# Grove_-_Sound_Sensor_v1_6.net
KiCad netlist of a schematic drawn in EAGLE
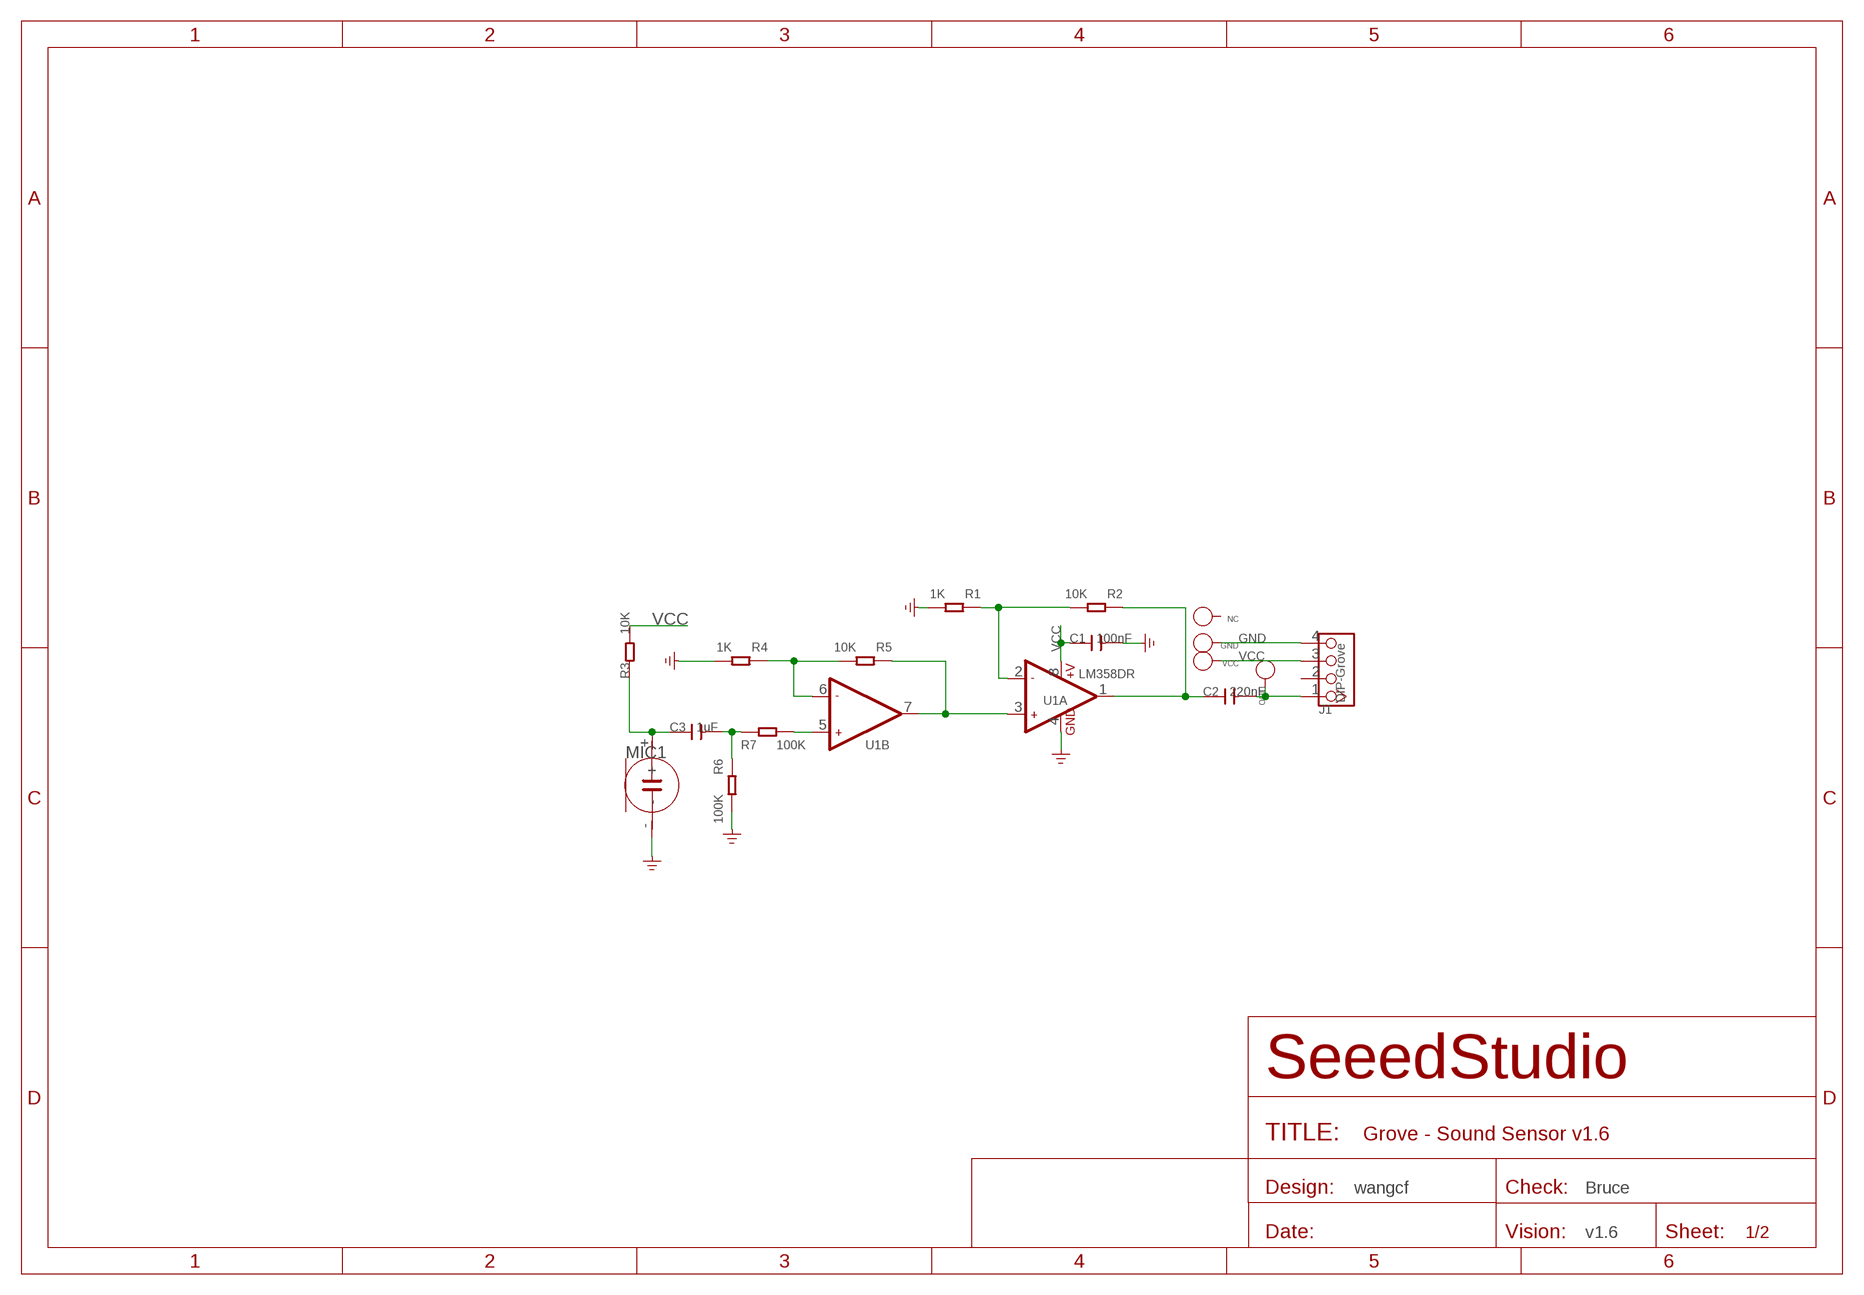
[diagram p0: schematic, sheet 1]
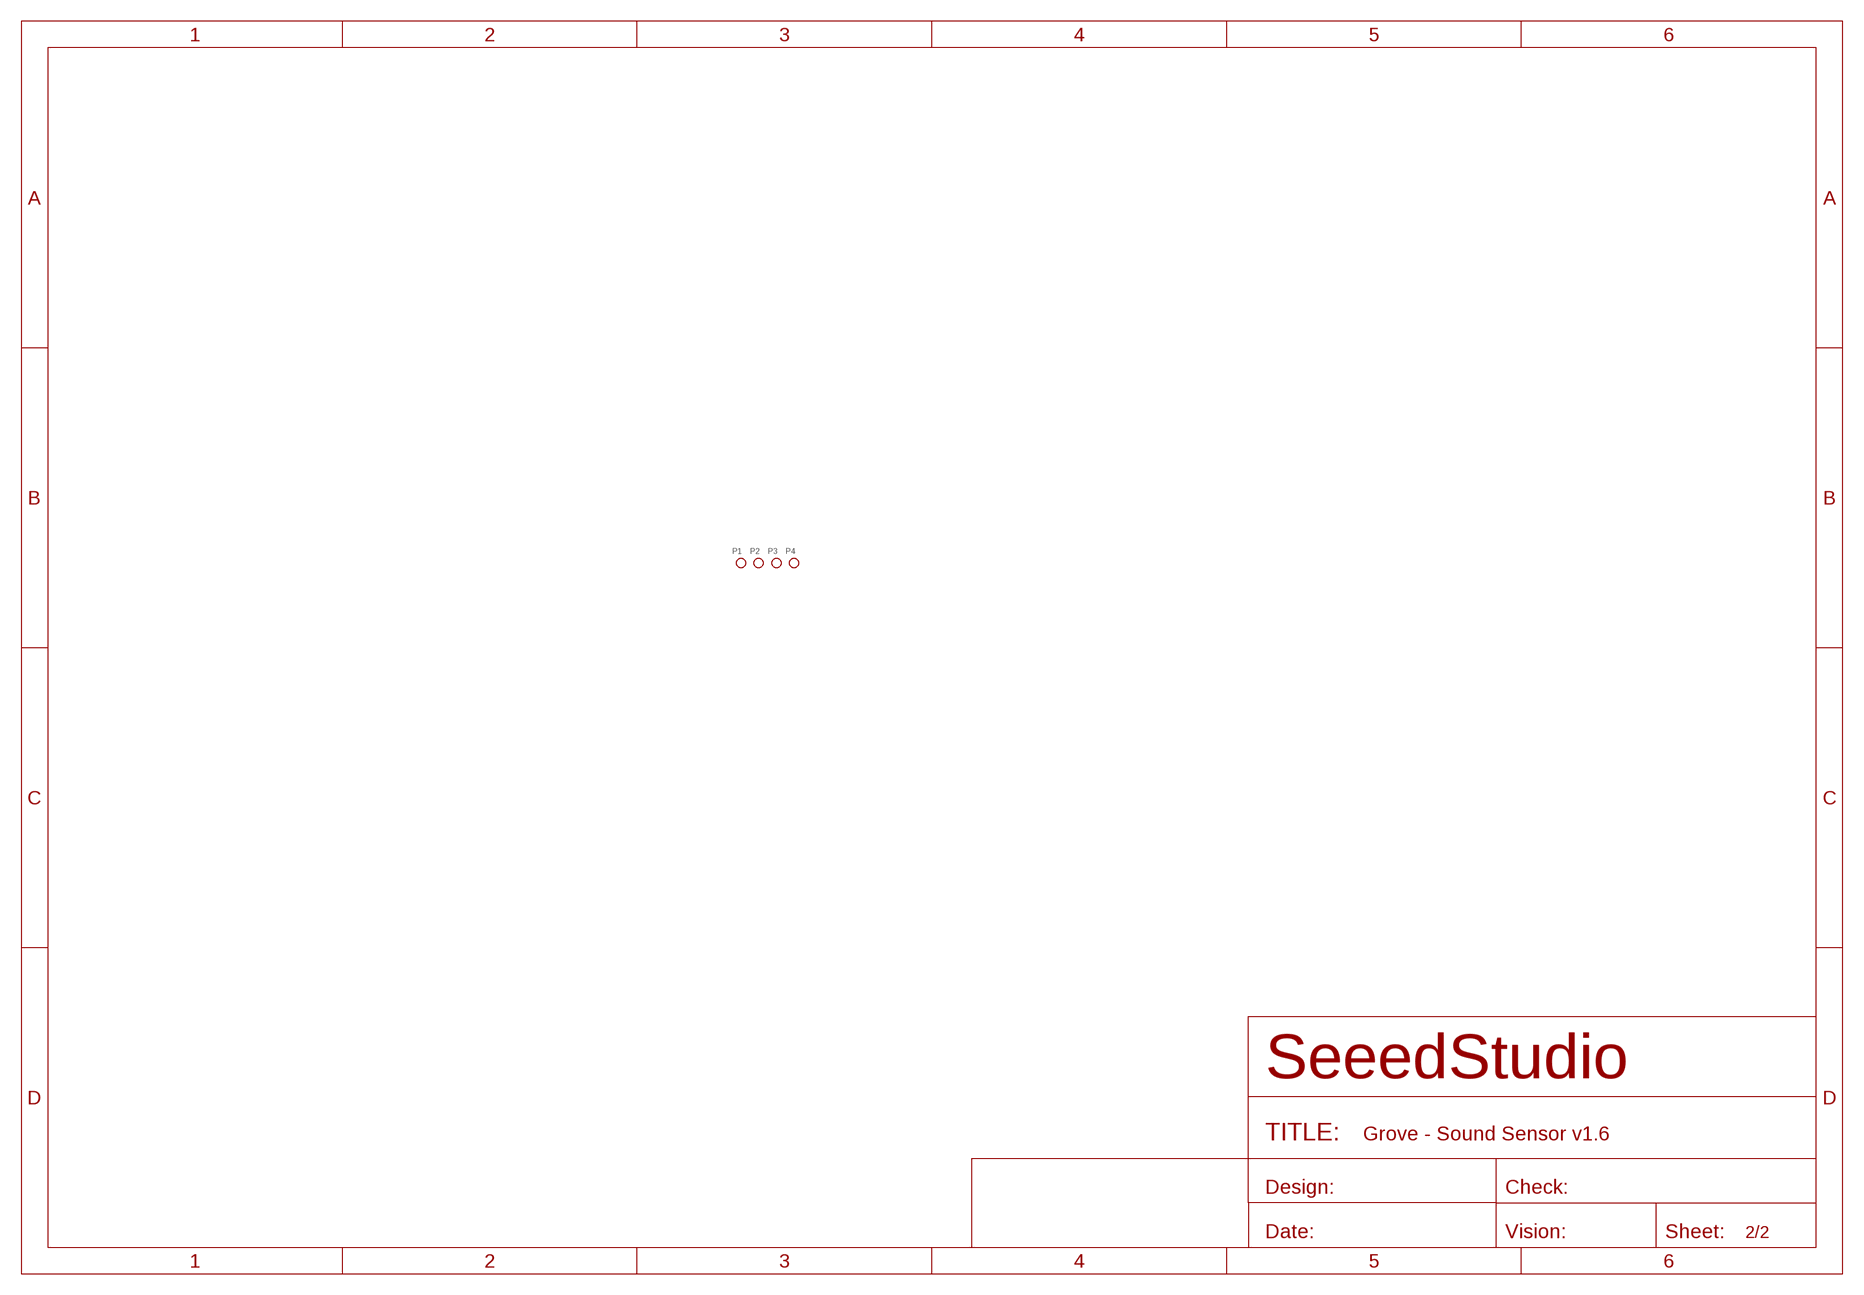
[diagram p1: schematic, sheet 2]

(export (version "E")
  (design (tool "Eeschema 10.0.6"))
  (components
    (comp (ref "P1")
      (value "PAD-MARK")
      (footprint "eagle-import:ROUND-MARK-1.0")
      (fields (field (name "PARTNO") "DNP"))
      (libsource (lib "eagle-import") (part "PAD-MARK"))
    )
    (comp (ref "P2")
      (value "PAD-MARK")
      (footprint "eagle-import:ROUND-MARK-1.0")
      (fields (field (name "PARTNO") "DNP"))
      (libsource (lib "eagle-import") (part "PAD-MARK"))
    )
    (comp (ref "P3")
      (value "PAD-MARK")
      (footprint "eagle-import:ROUND-MARK-1.0")
      (fields (field (name "PARTNO") "DNP"))
      (libsource (lib "eagle-import") (part "PAD-MARK"))
    )
    (comp (ref "P4")
      (value "PAD-MARK")
      (footprint "eagle-import:ROUND-MARK-1.0")
      (fields (field (name "PARTNO") "DNP"))
      (libsource (lib "eagle-import") (part "PAD-MARK"))
    )
    (comp (ref "C1")
      (value "100nF")
      (footprint "eagle-import:C0603")
      (libsource (lib "eagle-import") (part "C-0603"))
    )
    (comp (ref "C2")
      (value "220nF")
      (footprint "eagle-import:C0603")
      (libsource (lib "eagle-import") (part "C-0603"))
    )
    (comp (ref "C3")
      (value "1uF")
      (footprint "eagle-import:C0603")
      (libsource (lib "eagle-import") (part "C-0603"))
    )
    (comp (ref "GND")
      (value "PAD-TEST-POINT'4545'")
      (footprint "eagle-import:TP_4545")
      (fields (field (name "PARTNO") "DNP"))
      (libsource (lib "eagle-import") (part "PAD-TEST-POINT'4545'"))
    )
    (comp (ref "J1")
      (value "DIP-Grove")
      (footprint "eagle-import:4P-2.0")
      (libsource (lib "eagle-import") (part "TWIG-4P-2.0-2.0"))
    )
    (comp (ref "MIC1")
      (value "MICROPHONE'KS-9745P,-56DB'")
      (footprint "eagle-import:2P-D9.7_4.5H")
      (libsource (lib "eagle-import") (part "MICROPHONE'KS-9745P,-56DB'"))
    )
    (comp (ref "NC")
      (value "PAD-TEST-POINT'4545'")
      (footprint "eagle-import:TP_4545")
      (fields (field (name "PARTNO") "DNP"))
      (libsource (lib "eagle-import") (part "PAD-TEST-POINT'4545'"))
    )
    (comp (ref "OUT")
      (value "PAD-TEST-POINT'4545'")
      (footprint "eagle-import:TP_4545")
      (fields (field (name "PARTNO") "DNP"))
      (libsource (lib "eagle-import") (part "PAD-TEST-POINT'4545'"))
    )
    (comp (ref "R1")
      (value "1K")
      (footprint "eagle-import:R0603")
      (libsource (lib "eagle-import") (part "R-0603"))
    )
    (comp (ref "R2")
      (value "10K")
      (footprint "eagle-import:R0603")
      (libsource (lib "eagle-import") (part "R-0603"))
    )
    (comp (ref "R3")
      (value "10K")
      (footprint "eagle-import:R0603")
      (libsource (lib "eagle-import") (part "R-0603"))
    )
    (comp (ref "R4")
      (value "1K")
      (footprint "eagle-import:R0603")
      (libsource (lib "eagle-import") (part "R-0603"))
    )
    (comp (ref "R5")
      (value "10K")
      (footprint "eagle-import:R0603")
      (libsource (lib "eagle-import") (part "R-0603"))
    )
    (comp (ref "R6")
      (value "100K")
      (footprint "eagle-import:R0603")
      (libsource (lib "eagle-import") (part "R-0603"))
    )
    (comp (ref "R7")
      (value "100K")
      (footprint "eagle-import:R0603")
      (libsource (lib "eagle-import") (part "R-0603"))
    )
    (comp (ref "U1")
      (value "LM358DR")
      (footprint "eagle-import:SO08")
      (libsource (lib "eagle-import") (part "LMV358D"))
    )
    (comp (ref "VCC")
      (value "PAD-TEST-POINT'4545'")
      (footprint "eagle-import:TP_4545")
      (fields (field (name "PARTNO") "DNP"))
      (libsource (lib "eagle-import") (part "PAD-TEST-POINT'4545'"))
    )
  )
  (nets
    (net (code "1") (name "GND") (class "Default")
      (node (ref "C1") (pin "2") (pinfunction "2_2") (pintype "passive"))
      (node (ref "GND") (pin "T") (pinfunction "T_T") (pintype "bidirectional"))
      (node (ref "J1") (pin "4") (pinfunction "4_4") (pintype "bidirectional"))
      (node (ref "MIC1") (pin "-") (pinfunction "-_-") (pintype "bidirectional"))
      (node (ref "R1") (pin "2") (pinfunction "2_2") (pintype "passive"))
      (node (ref "R4") (pin "2") (pinfunction "2_2") (pintype "passive"))
      (node (ref "R6") (pin "2") (pinfunction "2_2") (pintype "passive"))
      (node (ref "U1") (pin "4") (pinfunction "GND_4") (pintype "power_in"))
    )
    (net (code "2") (name "Net-(C2-Pad2)") (class "Default")
      (node (ref "C2") (pin "2") (pinfunction "2_2") (pintype "passive"))
      (node (ref "J1") (pin "1") (pinfunction "1_1") (pintype "bidirectional"))
      (node (ref "OUT") (pin "T") (pinfunction "T_T") (pintype "bidirectional"))
    )
    (net (code "3") (name "Net-(C3-Pad1)") (class "Default")
      (node (ref "C3") (pin "1") (pinfunction "1_1") (pintype "passive"))
      (node (ref "MIC1") (pin "+") (pinfunction "+_+") (pintype "bidirectional"))
      (node (ref "R3") (pin "1") (pinfunction "1_1") (pintype "passive"))
    )
    (net (code "4") (name "Net-(C3-Pad2)") (class "Default")
      (node (ref "C3") (pin "2") (pinfunction "2_2") (pintype "passive"))
      (node (ref "R6") (pin "1") (pinfunction "1_1") (pintype "passive"))
      (node (ref "R7") (pin "1") (pinfunction "1_1") (pintype "passive"))
    )
    (net (code "5") (name "Net-(U1A-+IN1)") (class "Default")
      (node (ref "R5") (pin "1") (pinfunction "1_1") (pintype "passive"))
      (node (ref "U1") (pin "3") (pinfunction "+IN1_3") (pintype "input"))
      (node (ref "U1") (pin "7") (pinfunction "OUT2_7") (pintype "output"))
    )
    (net (code "6") (name "Net-(U1A--IN1)") (class "Default")
      (node (ref "R1") (pin "1") (pinfunction "1_1") (pintype "passive"))
      (node (ref "R2") (pin "2") (pinfunction "2_2") (pintype "passive"))
      (node (ref "U1") (pin "2") (pinfunction "-IN1_2") (pintype "input"))
    )
    (net (code "7") (name "Net-(U1A-OUT1)") (class "Default")
      (node (ref "C2") (pin "1") (pinfunction "1_1") (pintype "passive"))
      (node (ref "R2") (pin "1") (pinfunction "1_1") (pintype "passive"))
      (node (ref "U1") (pin "1") (pinfunction "OUT1_1") (pintype "output"))
    )
    (net (code "8") (name "Net-(U1B-+IN2)") (class "Default")
      (node (ref "R7") (pin "2") (pinfunction "2_2") (pintype "passive"))
      (node (ref "U1") (pin "5") (pinfunction "+IN2_5") (pintype "input"))
    )
    (net (code "9") (name "Net-(U1B--IN2)") (class "Default")
      (node (ref "R4") (pin "1") (pinfunction "1_1") (pintype "passive"))
      (node (ref "R5") (pin "2") (pinfunction "2_2") (pintype "passive"))
      (node (ref "U1") (pin "6") (pinfunction "-IN2_6") (pintype "input"))
    )
    (net (code "10") (name "VCC") (class "Default")
      (node (ref "C1") (pin "1") (pinfunction "1_1") (pintype "passive"))
      (node (ref "J1") (pin "3") (pinfunction "3_3") (pintype "bidirectional"))
      (node (ref "R3") (pin "2") (pinfunction "2_2") (pintype "passive"))
      (node (ref "U1") (pin "8") (pinfunction "+V_8") (pintype "power_in"))
      (node (ref "VCC") (pin "T") (pinfunction "T_T") (pintype "bidirectional"))
    )
    (net (code "11") (name "unconnected-(J1-Pad2)") (class "Default")
      (node (ref "J1") (pin "2") (pinfunction "2_2") (pintype "bidirectional"))
    )
    (net (code "12") (name "unconnected-(NC-PadT)") (class "Default")
      (node (ref "NC") (pin "T") (pinfunction "T_T") (pintype "bidirectional"))
    )
  )
)
